# IR_1E2R.net
KiCad netlist of a schematic drawn in EAGLE
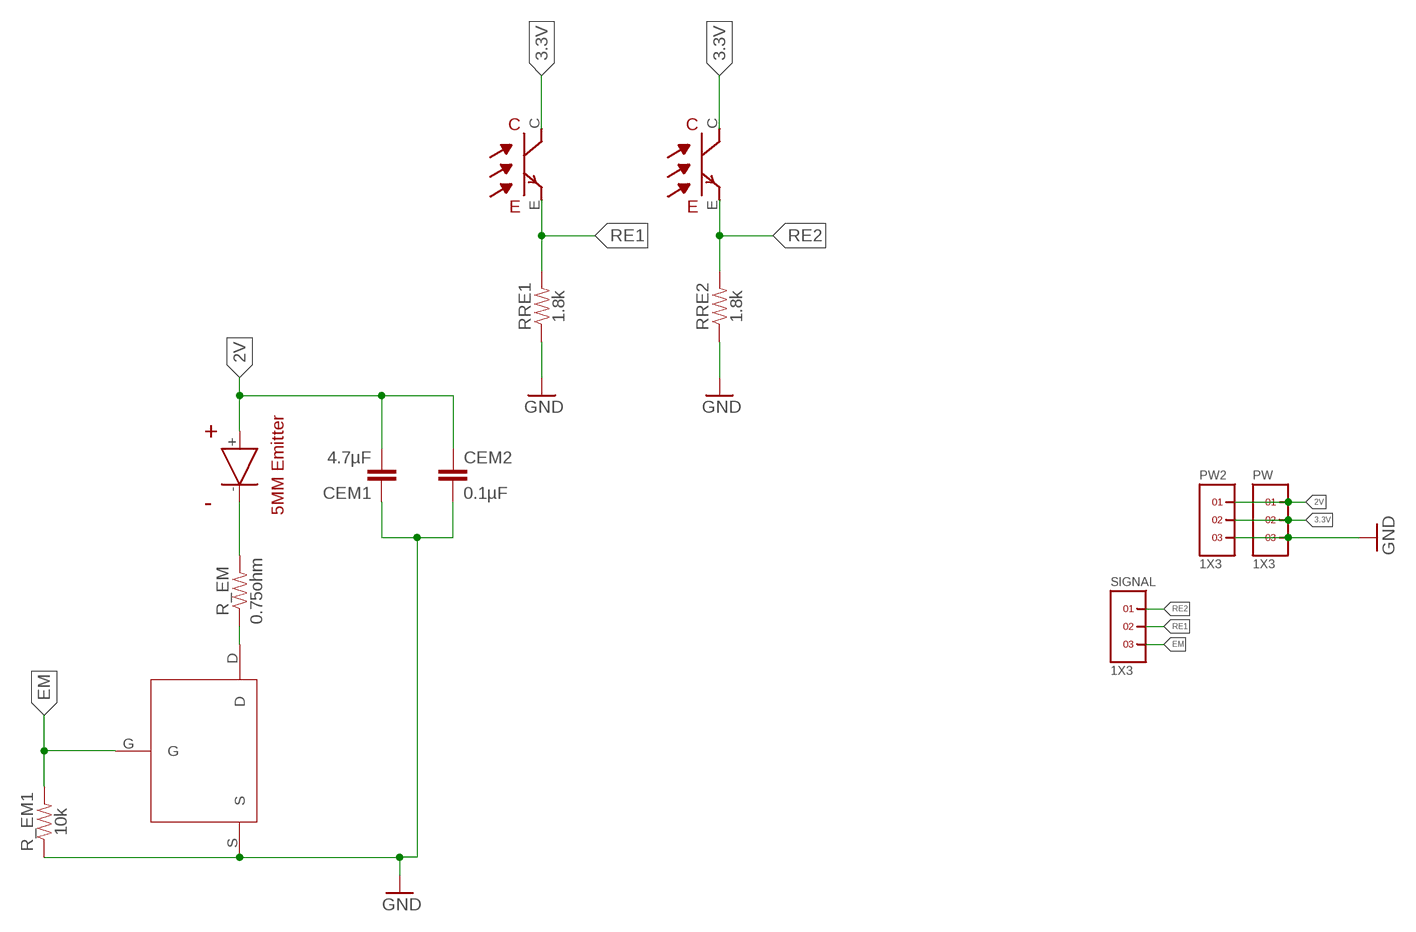
[diagram p0: schematic, sheet 1]

(export (version "E")
  (design (tool "Eeschema 10.0.6"))
  (components
    (comp (ref "CEM1")
      (value "4.7µF")
      (footprint "eagle-import:0805")
      (libsource (lib "eagle-import") (part "0.33UF/330NF-0805-50V-10%"))
    )
    (comp (ref "CEM2")
      (value "0.1µF")
      (footprint "eagle-import:0805")
      (libsource (lib "eagle-import") (part "0.33UF/330NF-0805-50V-10%"))
    )
    (comp (ref "PW")
      (value "1X3")
      (footprint "eagle-import:1X3")
      (libsource (lib "eagle-import") (part "1X3"))
    )
    (comp (ref "PW2")
      (value "1X3")
      (footprint "eagle-import:1X3")
      (libsource (lib "eagle-import") (part "1X3"))
    )
    (comp (ref "RECEIVER1")
      (value "RECEIVER")
      (footprint "eagle-import:RECEIVER")
      (libsource (lib "eagle-import") (part "RECEIVER"))
    )
    (comp (ref "RECEIVER2")
      (value "RECEIVER")
      (footprint "eagle-import:RECEIVER")
      (libsource (lib "eagle-import") (part "RECEIVER"))
    )
    (comp (ref "RRE1")
      (value "1.8k")
      (footprint "eagle-import:0805")
      (libsource (lib "eagle-import") (part "0.75OHM-0805-1/4W-1%"))
    )
    (comp (ref "RRE2")
      (value "1.8k")
      (footprint "eagle-import:0805")
      (libsource (lib "eagle-import") (part "0.75OHM-0805-1/4W-1%"))
    )
    (comp (ref "R_EM")
      (value "0.75ohm")
      (footprint "eagle-import:0805")
      (libsource (lib "eagle-import") (part "0.75OHM-0805-1/4W-1%"))
    )
    (comp (ref "R_EM1")
      (value "10k")
      (footprint "eagle-import:0805")
      (libsource (lib "eagle-import") (part "0.75OHM-0805-1/4W-1%"))
    )
    (comp (ref "SIGNAL")
      (value "1X3")
      (footprint "eagle-import:1X3")
      (libsource (lib "eagle-import") (part "1X3"))
    )
    (comp (ref "U$1")
      (value "MCH3474")
      (footprint "eagle-import:MCH3474")
      (libsource (lib "eagle-import") (part "MCH3474"))
    )
    (comp (ref "U$21")
      (value "EMITTER")
      (footprint "eagle-import:EMITTER")
      (libsource (lib "eagle-import") (part "EMITTER"))
    )
  )
  (nets
    (net (code "1") (name "2V") (class "Default")
      (node (ref "CEM1") (pin "2") (pinfunction "2_2") (pintype "passive"))
      (node (ref "CEM2") (pin "1") (pinfunction "1_1") (pintype "passive"))
      (node (ref "PW") (pin "1") (pinfunction "1_1") (pintype "bidirectional"))
      (node (ref "PW2") (pin "1") (pinfunction "1_1") (pintype "bidirectional"))
      (node (ref "U$21") (pin "+") (pinfunction "+_+") (pintype "bidirectional"))
    )
    (net (code "2") (name "3.3V") (class "Default")
      (node (ref "PW") (pin "2") (pinfunction "2_2") (pintype "bidirectional"))
      (node (ref "PW2") (pin "2") (pinfunction "2_2") (pintype "bidirectional"))
      (node (ref "RECEIVER1") (pin "C") (pinfunction "C_C") (pintype "bidirectional"))
      (node (ref "RECEIVER2") (pin "C") (pinfunction "C_C") (pintype "bidirectional"))
    )
    (net (code "3") (name "EM") (class "Default")
      (node (ref "R_EM1") (pin "2") (pinfunction "2_2") (pintype "passive"))
      (node (ref "SIGNAL") (pin "3") (pinfunction "3_3") (pintype "bidirectional"))
      (node (ref "U$1") (pin "G") (pinfunction "G_G") (pintype "bidirectional"))
    )
    (net (code "4") (name "GND") (class "Default")
      (node (ref "CEM1") (pin "1") (pinfunction "1_1") (pintype "passive"))
      (node (ref "CEM2") (pin "2") (pinfunction "2_2") (pintype "passive"))
      (node (ref "PW") (pin "3") (pinfunction "3_3") (pintype "bidirectional"))
      (node (ref "PW2") (pin "3") (pinfunction "3_3") (pintype "bidirectional"))
      (node (ref "RRE1") (pin "1") (pinfunction "1_1") (pintype "passive"))
      (node (ref "RRE2") (pin "1") (pinfunction "1_1") (pintype "passive"))
      (node (ref "R_EM1") (pin "1") (pinfunction "1_1") (pintype "passive"))
      (node (ref "U$1") (pin "S") (pinfunction "S_S") (pintype "bidirectional"))
    )
    (net (code "5") (name "Net-(R_EM-Pad1)") (class "Default")
      (node (ref "R_EM") (pin "1") (pinfunction "1_1") (pintype "passive"))
      (node (ref "U$1") (pin "D") (pinfunction "D_D") (pintype "bidirectional"))
    )
    (net (code "6") (name "Net-(R_EM-Pad2)") (class "Default")
      (node (ref "R_EM") (pin "2") (pinfunction "2_2") (pintype "passive"))
      (node (ref "U$21") (pin "-") (pinfunction "-_-") (pintype "bidirectional"))
    )
    (net (code "7") (name "RE1") (class "Default")
      (node (ref "RECEIVER1") (pin "E") (pinfunction "E_E") (pintype "bidirectional"))
      (node (ref "RRE1") (pin "2") (pinfunction "2_2") (pintype "passive"))
      (node (ref "SIGNAL") (pin "2") (pinfunction "2_2") (pintype "bidirectional"))
    )
    (net (code "8") (name "RE2") (class "Default")
      (node (ref "RECEIVER2") (pin "E") (pinfunction "E_E") (pintype "bidirectional"))
      (node (ref "RRE2") (pin "2") (pinfunction "2_2") (pintype "passive"))
      (node (ref "SIGNAL") (pin "1") (pinfunction "1_1") (pintype "bidirectional"))
    )
  )
)
